# 110_New_Top_Board.net
KiCad netlist of a schematic drawn in EAGLE
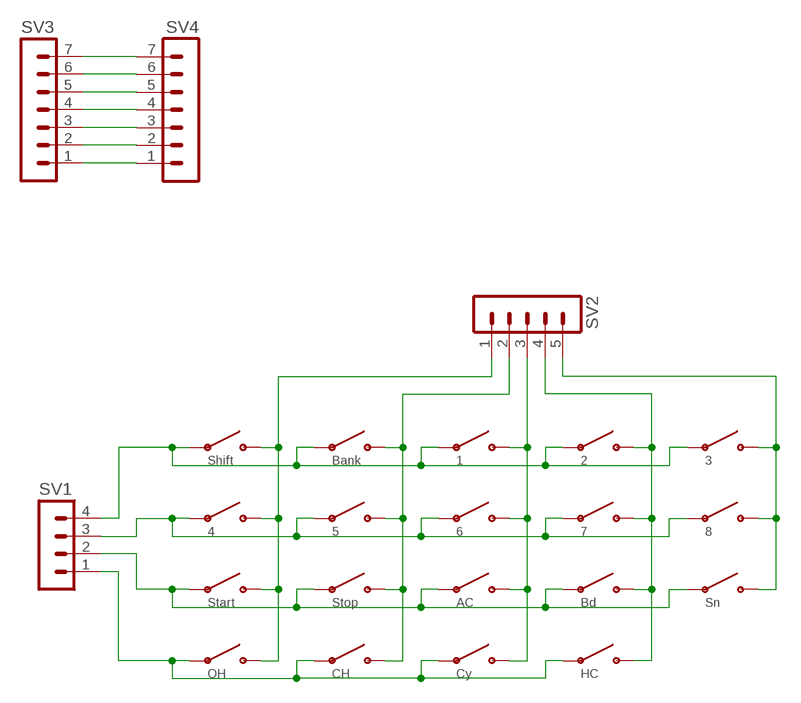
[diagram p0: schematic, sheet 1]

(export (version "E")
  (design (tool "Eeschema 10.0.6"))
  (components
    (comp (ref "SV1")
      (value "MA04-1")
      (footprint "eagle-import:MA04-1")
      (libsource (lib "eagle-import") (part "MA04-1"))
    )
    (comp (ref "SV2")
      (value "MA05-1")
      (footprint "eagle-import:MA05-1")
      (libsource (lib "eagle-import") (part "MA05-1"))
    )
    (comp (ref "SV3")
      (value "MA07-1")
      (footprint "eagle-import:MA07-1")
      (libsource (lib "eagle-import") (part "MA07-1"))
    )
    (comp (ref "SV4")
      (value "MA07-1")
      (footprint "eagle-import:MA07-1")
      (libsource (lib "eagle-import") (part "MA07-1"))
    )
    (comp (ref "U$1")
      (value "AC")
      (footprint "eagle-import:DR110-PAD")
      (libsource (lib "eagle-import") (part "DR110-BUTTON"))
    )
    (comp (ref "U$2")
      (value "Bd")
      (footprint "eagle-import:DR110-PAD")
      (libsource (lib "eagle-import") (part "DR110-BUTTON"))
    )
    (comp (ref "U$3")
      (value "Sn")
      (footprint "eagle-import:DR110-PAD")
      (libsource (lib "eagle-import") (part "DR110-BUTTON"))
    )
    (comp (ref "U$4")
      (value "OH")
      (footprint "eagle-import:DR110-PAD")
      (libsource (lib "eagle-import") (part "DR110-BUTTON"))
    )
    (comp (ref "U$5")
      (value "CH")
      (footprint "eagle-import:DR110-PAD")
      (libsource (lib "eagle-import") (part "DR110-BUTTON"))
    )
    (comp (ref "U$6")
      (value "Cy")
      (footprint "eagle-import:DR110-PAD")
      (libsource (lib "eagle-import") (part "DR110-BUTTON"))
    )
    (comp (ref "U$7")
      (value "HC")
      (footprint "eagle-import:DR110-PAD")
      (libsource (lib "eagle-import") (part "DR110-BUTTON"))
    )
    (comp (ref "U$8")
      (value "Shift")
      (footprint "eagle-import:DR110-PAD")
      (libsource (lib "eagle-import") (part "DR110-BUTTON"))
    )
    (comp (ref "U$9")
      (value "Bank")
      (footprint "eagle-import:DR110-PAD")
      (libsource (lib "eagle-import") (part "DR110-BUTTON"))
    )
    (comp (ref "U$10")
      (value "1")
      (footprint "eagle-import:DR110-PAD")
      (libsource (lib "eagle-import") (part "DR110-BUTTON"))
    )
    (comp (ref "U$11")
      (value "2")
      (footprint "eagle-import:DR110-PAD")
      (libsource (lib "eagle-import") (part "DR110-BUTTON"))
    )
    (comp (ref "U$12")
      (value "3")
      (footprint "eagle-import:DR110-PAD")
      (libsource (lib "eagle-import") (part "DR110-BUTTON"))
    )
    (comp (ref "U$13")
      (value "4")
      (footprint "eagle-import:DR110-PAD")
      (libsource (lib "eagle-import") (part "DR110-BUTTON"))
    )
    (comp (ref "U$14")
      (value "5")
      (footprint "eagle-import:DR110-PAD")
      (libsource (lib "eagle-import") (part "DR110-BUTTON"))
    )
    (comp (ref "U$15")
      (value "6")
      (footprint "eagle-import:DR110-PAD")
      (libsource (lib "eagle-import") (part "DR110-BUTTON"))
    )
    (comp (ref "U$16")
      (value "7")
      (footprint "eagle-import:DR110-PAD")
      (libsource (lib "eagle-import") (part "DR110-BUTTON"))
    )
    (comp (ref "U$17")
      (value "8")
      (footprint "eagle-import:DR110-PAD")
      (libsource (lib "eagle-import") (part "DR110-BUTTON"))
    )
    (comp (ref "U$19")
      (value "Start")
      (footprint "eagle-import:DR110-PAD")
      (libsource (lib "eagle-import") (part "DR110-BUTTON"))
    )
    (comp (ref "U$20")
      (value "Stop")
      (footprint "eagle-import:DR110-PAD")
      (libsource (lib "eagle-import") (part "DR110-BUTTON"))
    )
  )
  (nets
    (net (code "1") (name "Net-(SV1-Pad1)") (class "Default")
      (node (ref "SV1") (pin "1") (pinfunction "1_1") (pintype "passive"))
      (node (ref "U$4") (pin "P$1") (pinfunction "P$1_P$1") (pintype "bidirectional"))
      (node (ref "U$5") (pin "P$1") (pinfunction "P$1_P$1") (pintype "bidirectional"))
      (node (ref "U$6") (pin "P$1") (pinfunction "P$1_P$1") (pintype "bidirectional"))
      (node (ref "U$7") (pin "P$1") (pinfunction "P$1_P$1") (pintype "bidirectional"))
    )
    (net (code "2") (name "Net-(SV1-Pad2)") (class "Default")
      (node (ref "SV1") (pin "2") (pinfunction "2_2") (pintype "passive"))
      (node (ref "U$1") (pin "P$1") (pinfunction "P$1_P$1") (pintype "bidirectional"))
      (node (ref "U$19") (pin "P$1") (pinfunction "P$1_P$1") (pintype "bidirectional"))
      (node (ref "U$2") (pin "P$1") (pinfunction "P$1_P$1") (pintype "bidirectional"))
      (node (ref "U$20") (pin "P$1") (pinfunction "P$1_P$1") (pintype "bidirectional"))
      (node (ref "U$3") (pin "P$1") (pinfunction "P$1_P$1") (pintype "bidirectional"))
    )
    (net (code "3") (name "Net-(SV1-Pad3)") (class "Default")
      (node (ref "SV1") (pin "3") (pinfunction "3_3") (pintype "passive"))
      (node (ref "U$13") (pin "P$1") (pinfunction "P$1_P$1") (pintype "bidirectional"))
      (node (ref "U$14") (pin "P$1") (pinfunction "P$1_P$1") (pintype "bidirectional"))
      (node (ref "U$15") (pin "P$1") (pinfunction "P$1_P$1") (pintype "bidirectional"))
      (node (ref "U$16") (pin "P$1") (pinfunction "P$1_P$1") (pintype "bidirectional"))
      (node (ref "U$17") (pin "P$1") (pinfunction "P$1_P$1") (pintype "bidirectional"))
    )
    (net (code "4") (name "Net-(SV1-Pad4)") (class "Default")
      (node (ref "SV1") (pin "4") (pinfunction "4_4") (pintype "passive"))
      (node (ref "U$10") (pin "P$1") (pinfunction "P$1_P$1") (pintype "bidirectional"))
      (node (ref "U$11") (pin "P$1") (pinfunction "P$1_P$1") (pintype "bidirectional"))
      (node (ref "U$12") (pin "P$1") (pinfunction "P$1_P$1") (pintype "bidirectional"))
      (node (ref "U$8") (pin "P$1") (pinfunction "P$1_P$1") (pintype "bidirectional"))
      (node (ref "U$9") (pin "P$1") (pinfunction "P$1_P$1") (pintype "bidirectional"))
    )
    (net (code "5") (name "Net-(SV2-Pad1)") (class "Default")
      (node (ref "SV2") (pin "1") (pinfunction "1_1") (pintype "passive"))
      (node (ref "U$13") (pin "P$2") (pinfunction "P$2_P$2") (pintype "bidirectional"))
      (node (ref "U$19") (pin "P$2") (pinfunction "P$2_P$2") (pintype "bidirectional"))
      (node (ref "U$4") (pin "P$2") (pinfunction "P$2_P$2") (pintype "bidirectional"))
      (node (ref "U$8") (pin "P$2") (pinfunction "P$2_P$2") (pintype "bidirectional"))
    )
    (net (code "6") (name "Net-(SV2-Pad2)") (class "Default")
      (node (ref "SV2") (pin "2") (pinfunction "2_2") (pintype "passive"))
      (node (ref "U$14") (pin "P$2") (pinfunction "P$2_P$2") (pintype "bidirectional"))
      (node (ref "U$20") (pin "P$2") (pinfunction "P$2_P$2") (pintype "bidirectional"))
      (node (ref "U$5") (pin "P$2") (pinfunction "P$2_P$2") (pintype "bidirectional"))
      (node (ref "U$9") (pin "P$2") (pinfunction "P$2_P$2") (pintype "bidirectional"))
    )
    (net (code "7") (name "Net-(SV2-Pad3)") (class "Default")
      (node (ref "SV2") (pin "3") (pinfunction "3_3") (pintype "passive"))
      (node (ref "U$1") (pin "P$2") (pinfunction "P$2_P$2") (pintype "bidirectional"))
      (node (ref "U$10") (pin "P$2") (pinfunction "P$2_P$2") (pintype "bidirectional"))
      (node (ref "U$15") (pin "P$2") (pinfunction "P$2_P$2") (pintype "bidirectional"))
      (node (ref "U$6") (pin "P$2") (pinfunction "P$2_P$2") (pintype "bidirectional"))
    )
    (net (code "8") (name "Net-(SV2-Pad4)") (class "Default")
      (node (ref "SV2") (pin "4") (pinfunction "4_4") (pintype "passive"))
      (node (ref "U$11") (pin "P$2") (pinfunction "P$2_P$2") (pintype "bidirectional"))
      (node (ref "U$16") (pin "P$2") (pinfunction "P$2_P$2") (pintype "bidirectional"))
      (node (ref "U$2") (pin "P$2") (pinfunction "P$2_P$2") (pintype "bidirectional"))
      (node (ref "U$7") (pin "P$2") (pinfunction "P$2_P$2") (pintype "bidirectional"))
    )
    (net (code "9") (name "Net-(SV2-Pad5)") (class "Default")
      (node (ref "SV2") (pin "5") (pinfunction "5_5") (pintype "passive"))
      (node (ref "U$12") (pin "P$2") (pinfunction "P$2_P$2") (pintype "bidirectional"))
      (node (ref "U$17") (pin "P$2") (pinfunction "P$2_P$2") (pintype "bidirectional"))
      (node (ref "U$3") (pin "P$2") (pinfunction "P$2_P$2") (pintype "bidirectional"))
    )
    (net (code "10") (name "Net-(SV3-Pad1)") (class "Default")
      (node (ref "SV3") (pin "1") (pinfunction "1_1") (pintype "passive"))
      (node (ref "SV4") (pin "1") (pinfunction "1_1") (pintype "passive"))
    )
    (net (code "11") (name "Net-(SV3-Pad2)") (class "Default")
      (node (ref "SV3") (pin "2") (pinfunction "2_2") (pintype "passive"))
      (node (ref "SV4") (pin "2") (pinfunction "2_2") (pintype "passive"))
    )
    (net (code "12") (name "Net-(SV3-Pad3)") (class "Default")
      (node (ref "SV3") (pin "3") (pinfunction "3_3") (pintype "passive"))
      (node (ref "SV4") (pin "3") (pinfunction "3_3") (pintype "passive"))
    )
    (net (code "13") (name "Net-(SV3-Pad4)") (class "Default")
      (node (ref "SV3") (pin "4") (pinfunction "4_4") (pintype "passive"))
      (node (ref "SV4") (pin "4") (pinfunction "4_4") (pintype "passive"))
    )
    (net (code "14") (name "Net-(SV3-Pad5)") (class "Default")
      (node (ref "SV3") (pin "5") (pinfunction "5_5") (pintype "passive"))
      (node (ref "SV4") (pin "5") (pinfunction "5_5") (pintype "passive"))
    )
    (net (code "15") (name "Net-(SV3-Pad6)") (class "Default")
      (node (ref "SV3") (pin "6") (pinfunction "6_6") (pintype "passive"))
      (node (ref "SV4") (pin "6") (pinfunction "6_6") (pintype "passive"))
    )
    (net (code "16") (name "Net-(SV3-Pad7)") (class "Default")
      (node (ref "SV3") (pin "7") (pinfunction "7_7") (pintype "passive"))
      (node (ref "SV4") (pin "7") (pinfunction "7_7") (pintype "passive"))
    )
  )
)
